# 05_LMS1_Misc.net
KiCad netlist of a schematic drawn in Altium Designer
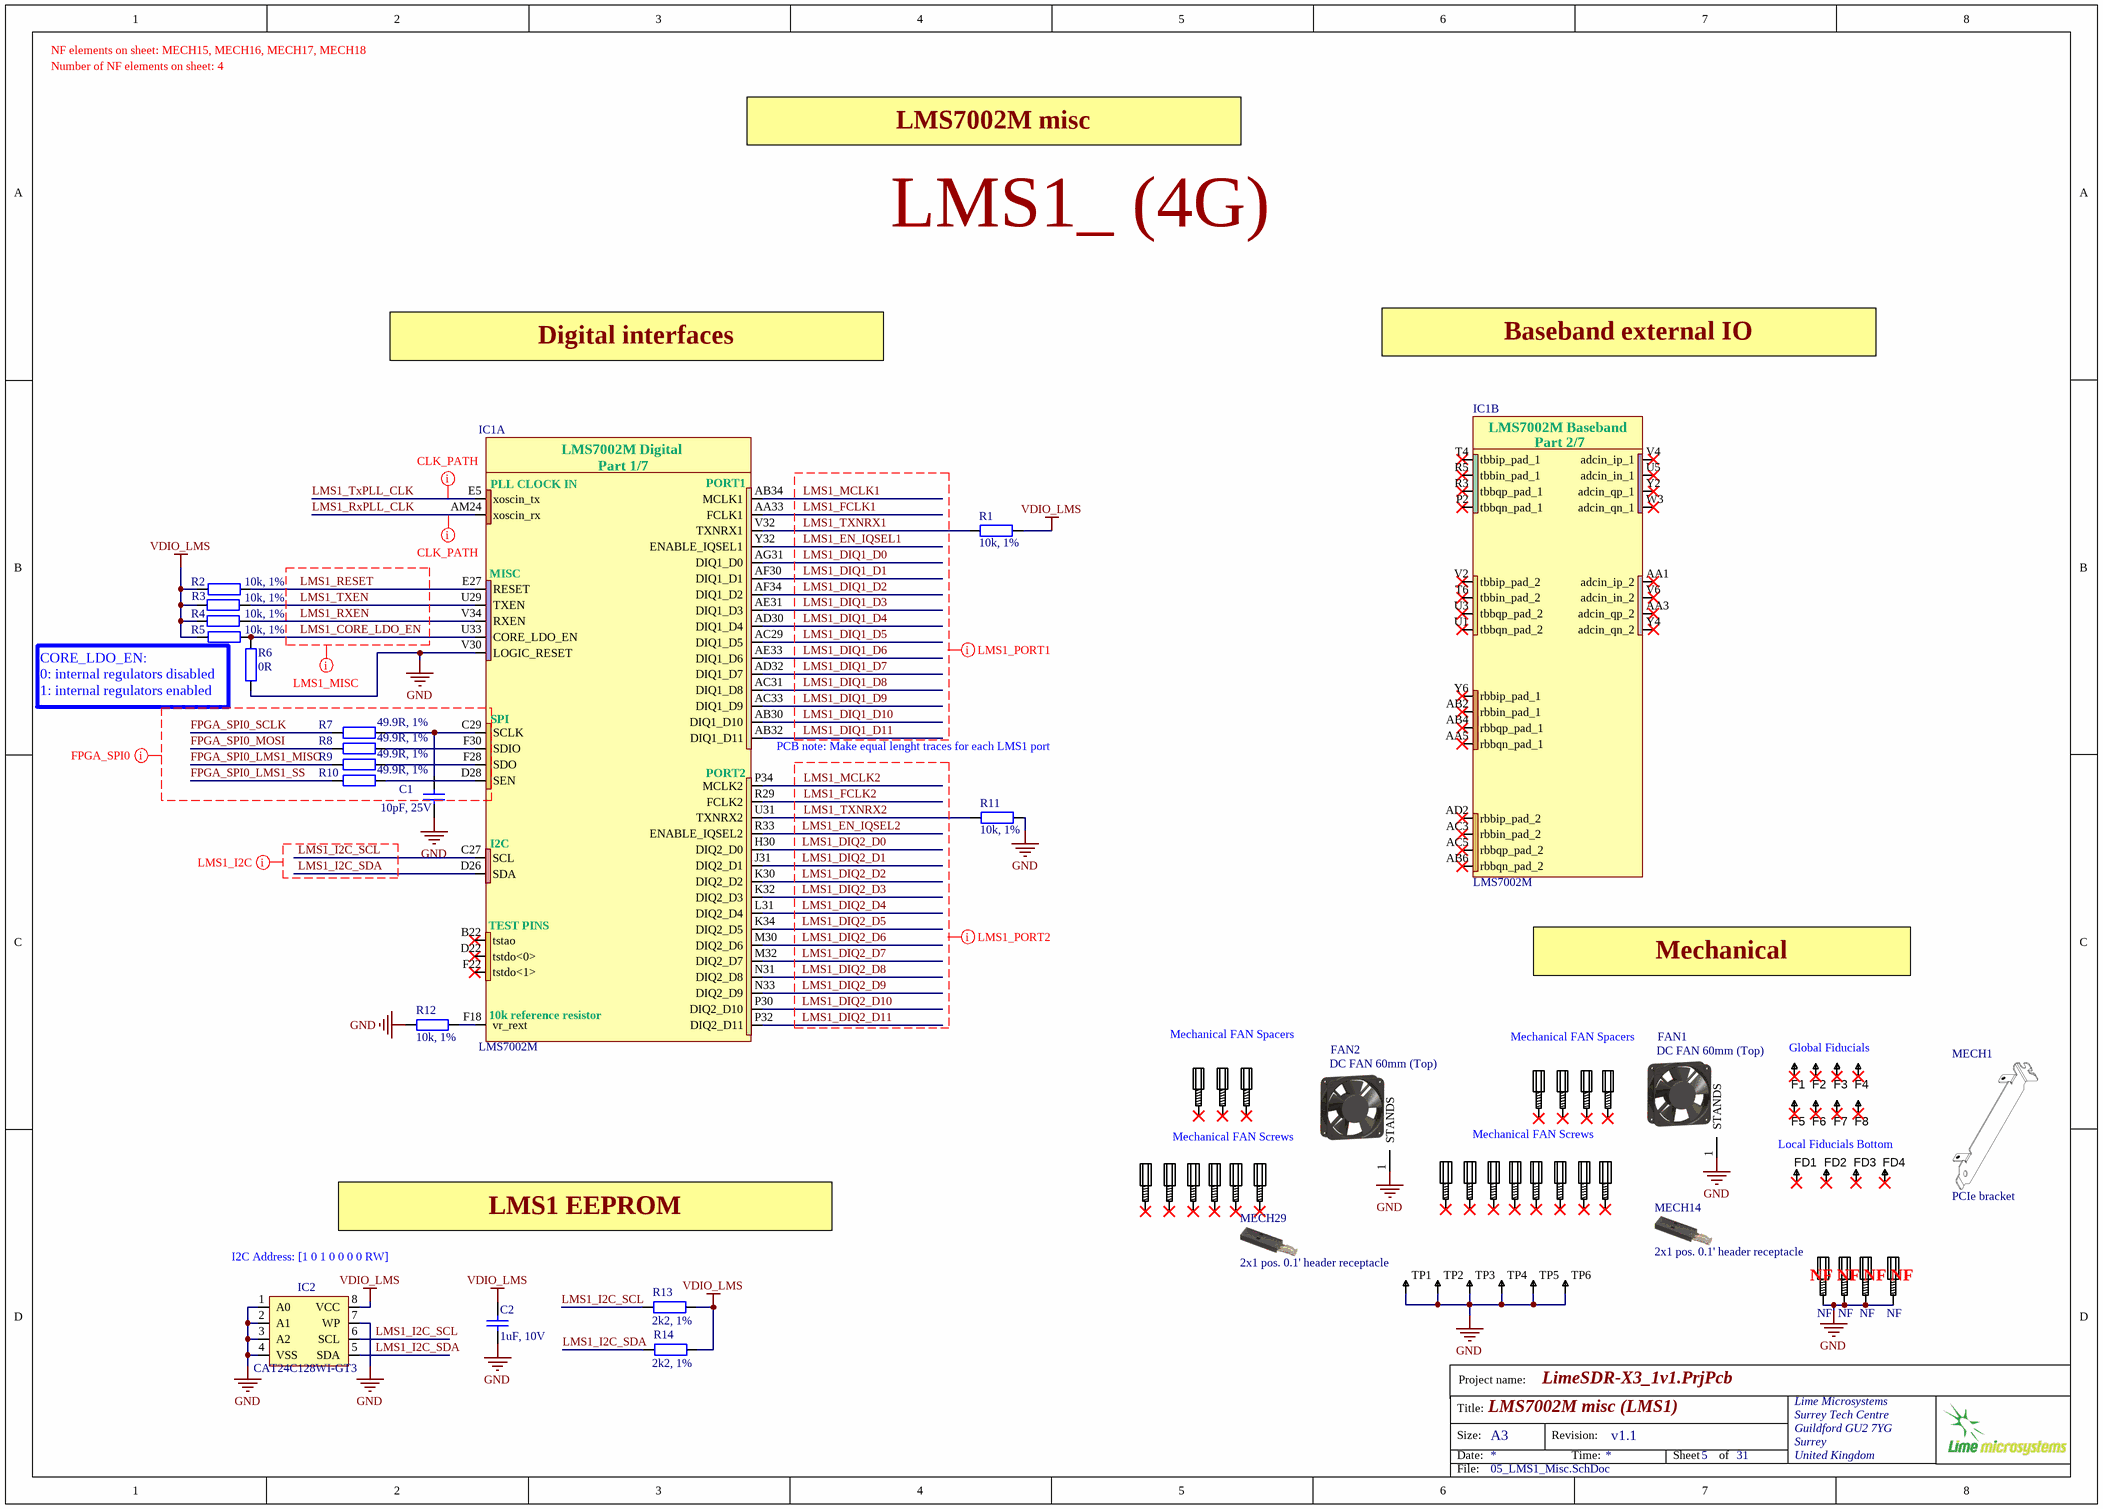
[diagram p0: 05_LMS1_Misc.SchDoc]

(export (version "E")
  (design (tool "Eeschema 10.0.6"))
  (components
    (comp (ref "C1")
      (value "10pF, 25V")
      (footprint "CAP0402")
      (fields (field (name "MANUFACTURER") "AVX"))
      (libsource (lib "") (part "Cap_0402_1"))
    )
    (comp (ref "C2")
      (value "1uF, 10V")
      (footprint "CAP0402")
      (fields (field (name "MANUFACTURER") "TDK"))
      (libsource (lib "LimeMicroAltiumLib_schLib") (part "Cap_0402"))
    )
    (comp (ref "F1")
      (value "Fiducial")
      (footprint "Fiducial")
      (libsource (lib "VGTU_Altium_lib") (part "Fiducial"))
    )
    (comp (ref "F2")
      (value "Fiducial")
      (footprint "Fiducial")
      (libsource (lib "VGTU_Altium_lib") (part "Fiducial"))
    )
    (comp (ref "F3")
      (value "Fiducial")
      (footprint "Fiducial")
      (libsource (lib "VGTU_Altium_lib") (part "Fiducial"))
    )
    (comp (ref "F4")
      (value "Fiducial")
      (footprint "Fiducial")
      (libsource (lib "VGTU_Altium_lib") (part "Fiducial"))
    )
    (comp (ref "F5")
      (value "Fiducial")
      (footprint "Fiducial")
      (libsource (lib "VGTU_Altium_lib") (part "Fiducial"))
    )
    (comp (ref "F6")
      (value "Fiducial")
      (footprint "Fiducial")
      (libsource (lib "VGTU_Altium_lib") (part "Fiducial"))
    )
    (comp (ref "F7")
      (value "Fiducial")
      (footprint "Fiducial")
      (libsource (lib "VGTU_Altium_lib") (part "Fiducial"))
    )
    (comp (ref "F8")
      (value "Fiducial")
      (footprint "Fiducial")
      (libsource (lib "VGTU_Altium_lib") (part "Fiducial"))
    )
    (comp (ref "FAN1")
      (value "DC FAN 60mm (Top)")
      (footprint "FAN_60mm")
      (fields (field (name "MANUFACTURER") "Sunon"))
      (libsource (lib "LimeMicroAltiumLib_schLib") (part "12V_DC_FAN"))
    )
    (comp (ref "FAN2")
      (value "DC FAN 60mm (Top)")
      (footprint "FAN_60mm")
      (fields (field (name "MANUFACTURER") "Sunon"))
      (libsource (lib "LimeMicroAltiumLib_schLib") (part "12V_DC_FAN"))
    )
    (comp (ref "FD1")
      (value "Fiducial")
      (footprint "Fiducial_local")
      (libsource (lib "") (part "Fiducial_1"))
    )
    (comp (ref "FD2")
      (value "Fiducial")
      (footprint "Fiducial_local")
      (libsource (lib "LimeMicroAltiumLib_schLib") (part "Fiducial"))
    )
    (comp (ref "FD3")
      (value "Fiducial")
      (footprint "Fiducial_local")
      (libsource (lib "") (part "Fiducial_2"))
    )
    (comp (ref "FD4")
      (value "Fiducial")
      (footprint "Fiducial_local")
      (libsource (lib "LimeMicroAltiumLib_schLib") (part "Fiducial"))
    )
    (comp (ref "IC1")
      (value "LMS7002M")
      (footprint "LMS7002M_v5")
      (description "Schematic symbol revision 4. Default footprint - 0.31mm pad")
      (fields (field (name "MANUFACTURER") "Lime Microsystems"))
      (libsource (lib "LimeMicroAltiumLib_schLib_r04") (part "LMS7002Mr4"))
    )
    (comp (ref "IC2")
      (value "CAT24C128WI-GT3")
      (footprint "SOIC127P600-8DL_v2")
      (fields (field (name "MANUFACTURER") "ON Semiconductor") (field (name "BASE PART NUMBER") "CAT24C128"))
      (libsource (lib "LimeMicroAltiumLib_schLib") (part "24FC64F"))
    )
    (comp (ref "MECH1")
      (value "PCIe bracket")
      (footprint "PCIe_bracket")
      (fields (field (name "MANUFACTURER") "Keystone Electronics"))
      (libsource (lib "LimeMicroAltiumLib_schLib_r01") (part "PCIe_bracket"))
    )
    (comp (ref "MECH2")
      (value "Spacer M3")
      (description "STANDOFF M/F MET 5MM HEX 10MM L")
      (fields (field (name "MANUFACTURER") "BOSSARD"))
      (libsource (lib "") (part "STANDOFF_M-F_THREADED_M3x8x10mm_HEX_5mm dia_1"))
    )
    (comp (ref "MECH3")
      (value "Spacer M3")
      (description "STANDOFF M/F MET 5MM HEX 10MM L")
      (fields (field (name "MANUFACTURER") "BOSSARD"))
      (libsource (lib "") (part "STANDOFF_M-F_THREADED_M3x8x10mm_HEX_5mm dia_1"))
    )
    (comp (ref "MECH4")
      (value "Spacer M3")
      (description "STANDOFF M/F MET 5MM HEX 10MM L")
      (fields (field (name "MANUFACTURER") "BOSSARD"))
      (libsource (lib "") (part "STANDOFF_M-F_THREADED_M3x8x10mm_HEX_5mm dia_1"))
    )
    (comp (ref "MECH5")
      (value "Spacer M3")
      (description "STANDOFF M/F MET 5MM HEX 10MM L")
      (fields (field (name "MANUFACTURER") "BOSSARD"))
      (libsource (lib "") (part "STANDOFF_M-F_THREADED_M3x8x10mm_HEX_5mm dia_1"))
    )
    (comp (ref "MECH6")
      (value "Screws M3")
      (description "STANDOFF M/F MET 5MM HEX 10MM L")
      (fields (field (name "MANUFACTURER") "BOSSARD"))
      (libsource (lib "LimeMicroAltiumLib_schLib") (part "STANDOFF_M-F_THREADED_M3x8x10mm_HEX_5mm dia"))
    )
    (comp (ref "MECH7")
      (value "Screws M3")
      (description "STANDOFF M/F MET 5MM HEX 10MM L")
      (fields (field (name "MANUFACTURER") "BOSSARD"))
      (libsource (lib "LimeMicroAltiumLib_schLib") (part "STANDOFF_M-F_THREADED_M3x8x10mm_HEX_5mm dia"))
    )
    (comp (ref "MECH8")
      (value "Screws M3")
      (description "STANDOFF M/F MET 5MM HEX 10MM L")
      (fields (field (name "MANUFACTURER") "BOSSARD"))
      (libsource (lib "LimeMicroAltiumLib_schLib") (part "STANDOFF_M-F_THREADED_M3x8x10mm_HEX_5mm dia"))
    )
    (comp (ref "MECH9")
      (value "Screws M3")
      (description "STANDOFF M/F MET 5MM HEX 10MM L")
      (fields (field (name "MANUFACTURER") "BOSSARD"))
      (libsource (lib "LimeMicroAltiumLib_schLib") (part "STANDOFF_M-F_THREADED_M3x8x10mm_HEX_5mm dia"))
    )
    (comp (ref "MECH10")
      (value "Screws M3")
      (description "STANDOFF M/F MET 5MM HEX 10MM L")
      (fields (field (name "MANUFACTURER") "BOSSARD"))
      (libsource (lib "LimeMicroAltiumLib_schLib") (part "STANDOFF_M-F_THREADED_M3x8x10mm_HEX_5mm dia"))
    )
    (comp (ref "MECH11")
      (value "Screws M3")
      (description "STANDOFF M/F MET 5MM HEX 10MM L")
      (fields (field (name "MANUFACTURER") "BOSSARD"))
      (libsource (lib "LimeMicroAltiumLib_schLib") (part "STANDOFF_M-F_THREADED_M3x8x10mm_HEX_5mm dia"))
    )
    (comp (ref "MECH12")
      (value "Screws M3")
      (description "STANDOFF M/F MET 5MM HEX 10MM L")
      (fields (field (name "MANUFACTURER") "BOSSARD"))
      (libsource (lib "LimeMicroAltiumLib_schLib") (part "STANDOFF_M-F_THREADED_M3x8x10mm_HEX_5mm dia"))
    )
    (comp (ref "MECH13")
      (value "Screws M3")
      (description "STANDOFF M/F MET 5MM HEX 10MM L")
      (fields (field (name "MANUFACTURER") "BOSSARD"))
      (libsource (lib "LimeMicroAltiumLib_schLib") (part "STANDOFF_M-F_THREADED_M3x8x10mm_HEX_5mm dia"))
    )
    (comp (ref "MECH14")
      (value "2x1 pos. 0.1' header receptacle")
      (fields (field (name "MANUFACTURER") "Molex"))
      (libsource (lib "LimeMicroAltiumLib_schLib_r01") (part "Header_1x2_receptacle"))
    )
    (comp (ref "MECH15")
      (value "Standoff")
      (footprint "PCB_standoff")
      (description "STANDOFF M/F MET 5MM HEX 10MM L")
      (fields (field (name "MANUFACTURER") "FIX&FASTEN") (field (name "ASSEMBLY INFO") "NF"))
      (libsource (lib "LimeMicroAltiumLib_schLib") (part "STANDOFF_M-F_THREADED_M3x8x10mm_HEX_5mm dia"))
    )
    (comp (ref "MECH16")
      (value "Standoff")
      (footprint "PCB_standoff")
      (description "STANDOFF M/F MET 5MM HEX 10MM L")
      (fields (field (name "MANUFACTURER") "FIX&FASTEN") (field (name "ASSEMBLY INFO") "NF"))
      (libsource (lib "LimeMicroAltiumLib_schLib") (part "STANDOFF_M-F_THREADED_M3x8x10mm_HEX_5mm dia"))
    )
    (comp (ref "MECH17")
      (value "Standoff")
      (footprint "PCB_standoff")
      (description "STANDOFF M/F MET 5MM HEX 10MM L")
      (fields (field (name "MANUFACTURER") "FIX&FASTEN") (field (name "ASSEMBLY INFO") "NF"))
      (libsource (lib "LimeMicroAltiumLib_schLib") (part "STANDOFF_M-F_THREADED_M3x8x10mm_HEX_5mm dia"))
    )
    (comp (ref "MECH18")
      (value "Standoff")
      (footprint "PCB_standoff")
      (description "STANDOFF M/F MET 5MM HEX 10MM L")
      (fields (field (name "MANUFACTURER") "FIX&FASTEN") (field (name "ASSEMBLY INFO") "NF"))
      (libsource (lib "") (part "STANDOFF_M-F_THREADED_M3x8x10mm_HEX_5mm dia_2"))
    )
    (comp (ref "MECH20")
      (value "Spacer M3")
      (description "STANDOFF M/F MET 5MM HEX 10MM L")
      (fields (field (name "MANUFACTURER") "BOSSARD"))
      (libsource (lib "") (part "STANDOFF_M-F_THREADED_M3x8x10mm_HEX_5mm dia_1"))
    )
    (comp (ref "MECH21")
      (value "Spacer M3")
      (description "STANDOFF M/F MET 5MM HEX 10MM L")
      (fields (field (name "MANUFACTURER") "BOSSARD"))
      (libsource (lib "") (part "STANDOFF_M-F_THREADED_M3x8x10mm_HEX_5mm dia_1"))
    )
    (comp (ref "MECH22")
      (value "Spacer M3")
      (description "STANDOFF M/F MET 5MM HEX 10MM L")
      (fields (field (name "MANUFACTURER") "BOSSARD"))
      (libsource (lib "") (part "STANDOFF_M-F_THREADED_M3x8x10mm_HEX_5mm dia_1"))
    )
    (comp (ref "MECH23")
      (value "Screws M3")
      (description "STANDOFF M/F MET 5MM HEX 10MM L")
      (fields (field (name "MANUFACTURER") "BOSSARD"))
      (libsource (lib "LimeMicroAltiumLib_schLib") (part "STANDOFF_M-F_THREADED_M3x8x10mm_HEX_5mm dia"))
    )
    (comp (ref "MECH24")
      (value "Screws M3")
      (description "STANDOFF M/F MET 5MM HEX 10MM L")
      (fields (field (name "MANUFACTURER") "BOSSARD"))
      (libsource (lib "LimeMicroAltiumLib_schLib") (part "STANDOFF_M-F_THREADED_M3x8x10mm_HEX_5mm dia"))
    )
    (comp (ref "MECH25")
      (value "Screws M3")
      (description "STANDOFF M/F MET 5MM HEX 10MM L")
      (fields (field (name "MANUFACTURER") "BOSSARD"))
      (libsource (lib "LimeMicroAltiumLib_schLib") (part "STANDOFF_M-F_THREADED_M3x8x10mm_HEX_5mm dia"))
    )
    (comp (ref "MECH26")
      (value "Screws M3")
      (description "STANDOFF M/F MET 5MM HEX 10MM L")
      (fields (field (name "MANUFACTURER") "BOSSARD"))
      (libsource (lib "LimeMicroAltiumLib_schLib") (part "STANDOFF_M-F_THREADED_M3x8x10mm_HEX_5mm dia"))
    )
    (comp (ref "MECH27")
      (value "Screws M3")
      (description "STANDOFF M/F MET 5MM HEX 10MM L")
      (fields (field (name "MANUFACTURER") "BOSSARD"))
      (libsource (lib "LimeMicroAltiumLib_schLib") (part "STANDOFF_M-F_THREADED_M3x8x10mm_HEX_5mm dia"))
    )
    (comp (ref "MECH28")
      (value "Screws M3")
      (description "STANDOFF M/F MET 5MM HEX 10MM L")
      (fields (field (name "MANUFACTURER") "BOSSARD"))
      (libsource (lib "LimeMicroAltiumLib_schLib") (part "STANDOFF_M-F_THREADED_M3x8x10mm_HEX_5mm dia"))
    )
    (comp (ref "MECH29")
      (value "2x1 pos. 0.1' header receptacle")
      (fields (field (name "MANUFACTURER") "Molex"))
      (libsource (lib "LimeMicroAltiumLib_schLib_r01") (part "Header_1x2_receptacle"))
    )
    (comp (ref "R1")
      (value "10k, 1%")
      (footprint "RES0402")
      (fields (field (name "MANUFACTURER") "Yageo") (field (name "TOLERANCE") "±1%"))
      (libsource (lib "LimeMicroAltiumLib_schLib") (part "Res_0402"))
    )
    (comp (ref "R2")
      (value "10k, 1%")
      (footprint "RES0402")
      (fields (field (name "MANUFACTURER") "Yageo") (field (name "TOLERANCE") "±1%"))
      (libsource (lib "LimeMicroAltiumLib_schLib") (part "Res_0402"))
    )
    (comp (ref "R3")
      (value "10k, 1%")
      (footprint "RES0402")
      (fields (field (name "MANUFACTURER") "Yageo") (field (name "TOLERANCE") "±1%"))
      (libsource (lib "LimeMicroAltiumLib_schLib") (part "Res_0402"))
    )
    (comp (ref "R4")
      (value "10k, 1%")
      (footprint "RES0402")
      (fields (field (name "MANUFACTURER") "Yageo") (field (name "TOLERANCE") "±1%"))
      (libsource (lib "LimeMicroAltiumLib_schLib") (part "Res_0402"))
    )
    (comp (ref "R5")
      (value "10k, 1%")
      (footprint "RES0402")
      (fields (field (name "MANUFACTURER") "Yageo") (field (name "TOLERANCE") "±1%"))
      (libsource (lib "LimeMicroAltiumLib_schLib") (part "Res_0402"))
    )
    (comp (ref "R6")
      (value "0R")
      (footprint "RES0402")
      (fields (field (name "MANUFACTURER") "Yageo") (field (name "TOLERANCE") "Jumper"))
      (libsource (lib "LimeMicroAltiumLib_schLib") (part "Res_0402"))
    )
    (comp (ref "R7")
      (value "49.9R, 1%")
      (footprint "RES0402")
      (fields
        (field (name "TOLERANCE") "±1%")
        (field (name "MANUFACTURER") "Samsung Electro-Mechanics America, Inc.")
        (field (name "MANUFACTURER PART NUMBER") "RC1005F49R9CS")
      )
      (libsource (lib "LimeMicroAltiumLib_schLib") (part "Res_0402"))
    )
    (comp (ref "R8")
      (value "49.9R, 1%")
      (footprint "RES0402")
      (fields
        (field (name "TOLERANCE") "±1%")
        (field (name "MANUFACTURER") "Samsung Electro-Mechanics America, Inc.")
        (field (name "MANUFACTURER PART NUMBER") "RC1005F49R9CS")
      )
      (libsource (lib "LimeMicroAltiumLib_schLib") (part "Res_0402"))
    )
    (comp (ref "R9")
      (value "49.9R, 1%")
      (footprint "RES0402")
      (fields
        (field (name "TOLERANCE") "±1%")
        (field (name "MANUFACTURER") "Samsung Electro-Mechanics America, Inc.")
        (field (name "MANUFACTURER PART NUMBER") "RC1005F49R9CS")
      )
      (libsource (lib "LimeMicroAltiumLib_schLib") (part "Res_0402"))
    )
    (comp (ref "R10")
      (value "49.9R, 1%")
      (footprint "RES0402")
      (fields
        (field (name "TOLERANCE") "±1%")
        (field (name "MANUFACTURER") "Samsung Electro-Mechanics America, Inc.")
        (field (name "MANUFACTURER PART NUMBER") "RC1005F49R9CS")
      )
      (libsource (lib "LimeMicroAltiumLib_schLib") (part "Res_0402"))
    )
    (comp (ref "R11")
      (value "10k, 1%")
      (footprint "RES0402")
      (fields (field (name "MANUFACTURER") "Yageo") (field (name "TOLERANCE") "±1%"))
      (libsource (lib "LimeMicroAltiumLib_schLib") (part "Res_0402"))
    )
    (comp (ref "R12")
      (value "10k, 1%")
      (footprint "RES0402")
      (fields (field (name "MANUFACTURER") "Yageo") (field (name "TOLERANCE") "±1%"))
      (libsource (lib "") (part "Res_0402_1"))
    )
    (comp (ref "R13")
      (value "2k2, 1%")
      (footprint "RES0402")
      (fields (field (name "MANUFACTURER") "Stackpole Electronics Inc") (field (name "TOLERANCE") "±1%"))
      (libsource (lib "LimeMicroAltiumLib_schLib") (part "Res_0402"))
    )
    (comp (ref "R14")
      (value "2k2, 1%")
      (footprint "RES0402")
      (fields (field (name "MANUFACTURER") "Stackpole Electronics Inc") (field (name "TOLERANCE") "±1%"))
      (libsource (lib "LimeMicroAltiumLib_schLib") (part "Res_0402"))
    )
    (comp (ref "TP1")
      (value "TESTPOINT_THT_MINI")
      (footprint "TP-SMD-LOW_PROFILE")
      (description "Test Point PCB mount Miniature White")
      (fields (field (name "MANUFACTURER") "Harwin Inc"))
      (libsource (lib "LimeMicroAltiumLib_schLib") (part "TESTPOINT_THT_MINI"))
    )
    (comp (ref "TP2")
      (value "TESTPOINT_THT_MINI")
      (footprint "TP-SMD-LOW_PROFILE")
      (description "Test Point PCB mount Miniature White")
      (fields (field (name "MANUFACTURER") "Harwin Inc"))
      (libsource (lib "LimeMicroAltiumLib_schLib") (part "TESTPOINT_THT_MINI"))
    )
    (comp (ref "TP3")
      (value "TESTPOINT_THT_MINI")
      (footprint "TP-SMD-LOW_PROFILE")
      (description "Test Point PCB mount Miniature White")
      (fields (field (name "MANUFACTURER") "Harwin Inc"))
      (libsource (lib "LimeMicroAltiumLib_schLib") (part "TESTPOINT_THT_MINI"))
    )
    (comp (ref "TP4")
      (value "TESTPOINT_THT_MINI")
      (footprint "TP-SMD-LOW_PROFILE")
      (description "Test Point PCB mount Miniature White")
      (fields (field (name "MANUFACTURER") "Harwin Inc"))
      (libsource (lib "LimeMicroAltiumLib_schLib") (part "TESTPOINT_THT_MINI"))
    )
    (comp (ref "TP5")
      (value "TESTPOINT_THT_MINI")
      (footprint "TP-SMD-LOW_PROFILE")
      (description "Test Point PCB mount Miniature White")
      (fields (field (name "MANUFACTURER") "Harwin Inc"))
      (libsource (lib "LimeMicroAltiumLib_schLib") (part "TESTPOINT_THT_MINI"))
    )
    (comp (ref "TP6")
      (value "TESTPOINT_THT_MINI")
      (footprint "TP-SMD-LOW_PROFILE")
      (description "Test Point PCB mount Miniature White")
      (fields (field (name "MANUFACTURER") "Harwin Inc"))
      (libsource (lib "LimeMicroAltiumLib_schLib") (part "TESTPOINT_THT_MINI"))
    )
  )
  (nets
    (net (code "1") (name "/FPGA_SPI0_LMS1_MISO") (class "Default")
      (node (ref "R9") (pin "2") (pinfunction "2_2") (pintype "passive"))
    )
    (net (code "2") (name "/FPGA_SPI0_LMS1_SS") (class "Default")
      (node (ref "R10") (pin "2") (pinfunction "2_2") (pintype "passive"))
    )
    (net (code "3") (name "/FPGA_SPI0_MOSI") (class "Default")
      (node (ref "R8") (pin "2") (pinfunction "2_2") (pintype "passive"))
    )
    (net (code "4") (name "/FPGA_SPI0_SCLK") (class "Default")
      (node (ref "R7") (pin "2") (pinfunction "2_2") (pintype "passive"))
    )
    (net (code "5") (name "/LMS1_CORE_LDO_EN") (class "Default")
      (node (ref "IC1") (pin "U33") (pinfunction "CORE_LDO_EN_U33") (pintype "passive"))
      (node (ref "R5") (pin "1") (pinfunction "1_1") (pintype "passive"))
      (node (ref "R6") (pin "2") (pinfunction "2_2") (pintype "passive"))
    )
    (net (code "6") (name "/LMS1_DIQ1_D0") (class "Default")
      (node (ref "IC1") (pin "AG31") (pinfunction "DIQ1_D0_AG31") (pintype "passive"))
    )
    (net (code "7") (name "/LMS1_DIQ1_D1") (class "Default")
      (node (ref "IC1") (pin "AF30") (pinfunction "DIQ1_D1_AF30") (pintype "passive"))
    )
    (net (code "8") (name "/LMS1_DIQ1_D2") (class "Default")
      (node (ref "IC1") (pin "AF34") (pinfunction "DIQ1_D2_AF34") (pintype "passive"))
    )
    (net (code "9") (name "/LMS1_DIQ1_D3") (class "Default")
      (node (ref "IC1") (pin "AE31") (pinfunction "DIQ1_D3_AE31") (pintype "passive"))
    )
    (net (code "10") (name "/LMS1_DIQ1_D4") (class "Default")
      (node (ref "IC1") (pin "AD30") (pinfunction "DIQ1_D4_AD30") (pintype "passive"))
    )
    (net (code "11") (name "/LMS1_DIQ1_D5") (class "Default")
      (node (ref "IC1") (pin "AC29") (pinfunction "DIQ1_D5_AC29") (pintype "passive"))
    )
    (net (code "12") (name "/LMS1_DIQ1_D6") (class "Default")
      (node (ref "IC1") (pin "AE33") (pinfunction "DIQ1_D6_AE33") (pintype "passive"))
    )
    (net (code "13") (name "/LMS1_DIQ1_D7") (class "Default")
      (node (ref "IC1") (pin "AD32") (pinfunction "DIQ1_D7_AD32") (pintype "passive"))
    )
    (net (code "14") (name "/LMS1_DIQ1_D8") (class "Default")
      (node (ref "IC1") (pin "AC31") (pinfunction "DIQ1_D8_AC31") (pintype "passive"))
    )
    (net (code "15") (name "/LMS1_DIQ1_D9") (class "Default")
      (node (ref "IC1") (pin "AC33") (pinfunction "DIQ1_D9_AC33") (pintype "passive"))
    )
    (net (code "16") (name "/LMS1_DIQ1_D10") (class "Default")
      (node (ref "IC1") (pin "AB30") (pinfunction "DIQ1_D10_AB30") (pintype "passive"))
    )
    (net (code "17") (name "/LMS1_DIQ1_D11") (class "Default")
      (node (ref "IC1") (pin "AB32") (pinfunction "DIQ1_D11_AB32") (pintype "passive"))
    )
    (net (code "18") (name "/LMS1_DIQ2_D0") (class "Default")
      (node (ref "IC1") (pin "H30") (pinfunction "DIQ2_D0_H30") (pintype "passive"))
    )
    (net (code "19") (name "/LMS1_DIQ2_D1") (class "Default")
      (node (ref "IC1") (pin "J31") (pinfunction "DIQ2_D1_J31") (pintype "passive"))
    )
    (net (code "20") (name "/LMS1_DIQ2_D2") (class "Default")
      (node (ref "IC1") (pin "K30") (pinfunction "DIQ2_D2_K30") (pintype "passive"))
    )
    (net (code "21") (name "/LMS1_DIQ2_D3") (class "Default")
      (node (ref "IC1") (pin "K32") (pinfunction "DIQ2_D3_K32") (pintype "passive"))
    )
    (net (code "22") (name "/LMS1_DIQ2_D4") (class "Default")
      (node (ref "IC1") (pin "L31") (pinfunction "DIQ2_D4_L31") (pintype "passive"))
    )
    (net (code "23") (name "/LMS1_DIQ2_D5") (class "Default")
      (node (ref "IC1") (pin "K34") (pinfunction "DIQ2_D5_K34") (pintype "passive"))
    )
    (net (code "24") (name "/LMS1_DIQ2_D6") (class "Default")
      (node (ref "IC1") (pin "M30") (pinfunction "DIQ2_D6_M30") (pintype "passive"))
    )
    (net (code "25") (name "/LMS1_DIQ2_D7") (class "Default")
      (node (ref "IC1") (pin "M32") (pinfunction "DIQ2_D7_M32") (pintype "passive"))
    )
    (net (code "26") (name "/LMS1_DIQ2_D8") (class "Default")
      (node (ref "IC1") (pin "N31") (pinfunction "DIQ2_D8_N31") (pintype "passive"))
    )
    (net (code "27") (name "/LMS1_DIQ2_D9") (class "Default")
      (node (ref "IC1") (pin "N33") (pinfunction "DIQ2_D9_N33") (pintype "passive"))
    )
    (net (code "28") (name "/LMS1_DIQ2_D10") (class "Default")
      (node (ref "IC1") (pin "P30") (pinfunction "DIQ2_D10_P30") (pintype "passive"))
    )
    (net (code "29") (name "/LMS1_DIQ2_D11") (class "Default")
      (node (ref "IC1") (pin "P32") (pinfunction "DIQ2_D11_P32") (pintype "passive"))
    )
    (net (code "30") (name "/LMS1_EN_IQSEL1") (class "Default")
      (node (ref "IC1") (pin "Y32") (pinfunction "ENABLE_IQSEL1_Y32") (pintype "passive"))
    )
    (net (code "31") (name "/LMS1_EN_IQSEL2") (class "Default")
      (node (ref "IC1") (pin "R33") (pinfunction "ENABLE_IQSEL2_R33") (pintype "passive"))
    )
    (net (code "32") (name "/LMS1_FCLK1") (class "Default")
      (node (ref "IC1") (pin "AA33") (pinfunction "FCLK1_AA33") (pintype "passive"))
    )
    (net (code "33") (name "/LMS1_FCLK2") (class "Default")
      (node (ref "IC1") (pin "R29") (pinfunction "FCLK2_R29") (pintype "passive"))
    )
    (net (code "34") (name "/LMS1_I2C_SCL") (class "Default")
      (node (ref "IC1") (pin "C27") (pinfunction "SCL_C27") (pintype "passive"))
      (node (ref "IC2") (pin "6") (pinfunction "SCL_6") (pintype "passive"))
      (node (ref "R13") (pin "2") (pinfunction "2_2") (pintype "passive"))
    )
    (net (code "35") (name "/LMS1_I2C_SDA") (class "Default")
      (node (ref "IC1") (pin "D26") (pinfunction "SDA_D26") (pintype "passive"))
      (node (ref "IC2") (pin "5") (pinfunction "SDA_5") (pintype "passive"))
      (node (ref "R14") (pin "2") (pinfunction "2_2") (pintype "passive"))
    )
    (net (code "36") (name "/LMS1_MCLK1") (class "Default")
      (node (ref "IC1") (pin "AB34") (pinfunction "MCLK1_AB34") (pintype "passive"))
    )
    (net (code "37") (name "/LMS1_MCLK2") (class "Default")
      (node (ref "IC1") (pin "P34") (pinfunction "MCLK2_P34") (pintype "passive"))
    )
    (net (code "38") (name "/LMS1_RESET") (class "Default")
      (node (ref "IC1") (pin "E27") (pinfunction "RESET_E27") (pintype "passive"))
      (node (ref "R2") (pin "1") (pinfunction "1_1") (pintype "passive"))
    )
    (net (code "39") (name "/LMS1_RXEN") (class "Default")
      (node (ref "IC1") (pin "V34") (pinfunction "RXEN_V34") (pintype "passive"))
      (node (ref "R4") (pin "2") (pinfunction "2_2") (pintype "passive"))
    )
    (net (code "40") (name "/LMS1_RxPLL_CLK") (class "Default")
      (node (ref "IC1") (pin "AM24") (pinfunction "xoscin_rx_AM24") (pintype "passive"))
    )
    (net (code "41") (name "/LMS1_TXEN") (class "Default")
      (node (ref "IC1") (pin "U29") (pinfunction "TXEN_U29") (pintype "passive"))
      (node (ref "R3") (pin "2") (pinfunction "2_2") (pintype "passive"))
    )
    (net (code "42") (name "/LMS1_TXNRX1") (class "Default")
      (node (ref "IC1") (pin "V32") (pinfunction "TXNRX1_V32") (pintype "passive"))
      (node (ref "R1") (pin "1") (pinfunction "1_1") (pintype "passive"))
    )
    (net (code "43") (name "/LMS1_TXNRX2") (class "Default")
      (node (ref "IC1") (pin "U31") (pinfunction "TXNRX2_U31") (pintype "passive"))
      (node (ref "R11") (pin "2") (pinfunction "2_2") (pintype "passive"))
    )
    (net (code "44") (name "/LMS1_TxPLL_CLK") (class "Default")
      (node (ref "IC1") (pin "E5") (pinfunction "xoscin_tx_E5") (pintype "passive"))
    )
    (net (code "45") (name "GND") (class "Default")
      (node (ref "C1") (pin "2") (pinfunction "2_2") (pintype "passive"))
      (node (ref "C2") (pin "2") (pinfunction "2_2") (pintype "passive"))
      (node (ref "FAN1") (pin "1") (pinfunction "STANDS_1") (pintype "passive"))
      (node (ref "FAN2") (pin "1") (pinfunction "STANDS_1") (pintype "passive"))
      (node (ref "IC1") (pin "V30") (pinfunction "LOGIC_RESET_V30") (pintype "passive"))
      (node (ref "IC2") (pin "1") (pinfunction "A0_1") (pintype "passive"))
      (node (ref "IC2") (pin "2") (pinfunction "A1_2") (pintype "passive"))
      (node (ref "IC2") (pin "3") (pinfunction "A2_3") (pintype "passive"))
      (node (ref "IC2") (pin "4") (pinfunction "VSS_4") (pintype "passive"))
      (node (ref "IC2") (pin "7") (pinfunction "WP_7") (pintype "passive"))
      (node (ref "MECH15") (pin "MH1") (pinfunction "MH1_MH1") (pintype "passive"))
      (node (ref "MECH16") (pin "MH1") (pinfunction "MH1_MH1") (pintype "passive"))
      (node (ref "MECH17") (pin "MH1") (pinfunction "MH1_MH1") (pintype "passive"))
      (node (ref "MECH18") (pin "MH1") (pinfunction "MH1_MH1") (pintype "passive"))
      (node (ref "R11") (pin "1") (pinfunction "1_1") (pintype "passive"))
      (node (ref "R12") (pin "2") (pinfunction "2_2") (pintype "passive"))
      (node (ref "R6") (pin "1") (pinfunction "1_1") (pintype "passive"))
      (node (ref "TP1") (pin "1") (pintype "passive"))
      (node (ref "TP2") (pin "1") (pintype "passive"))
      (node (ref "TP3") (pin "1") (pintype "passive"))
      (node (ref "TP4") (pin "1") (pintype "passive"))
      (node (ref "TP5") (pin "1") (pintype "passive"))
      (node (ref "TP6") (pin "1") (pintype "passive"))
    )
    (net (code "46") (name "Net-(IC1A-SCLK)") (class "Default")
      (node (ref "C1") (pin "1") (pinfunction "1_1") (pintype "passive"))
      (node (ref "IC1") (pin "C29") (pinfunction "SCLK_C29") (pintype "passive"))
      (node (ref "R7") (pin "1") (pinfunction "1_1") (pintype "passive"))
    )
    (net (code "47") (name "Net-(IC1A-SDIO)") (class "Default")
      (node (ref "IC1") (pin "F30") (pinfunction "SDIO_F30") (pintype "passive"))
      (node (ref "R8") (pin "1") (pinfunction "1_1") (pintype "passive"))
    )
    (net (code "48") (name "Net-(IC1A-SDO)") (class "Default")
      (node (ref "IC1") (pin "F28") (pinfunction "SDO_F28") (pintype "passive"))
      (node (ref "R9") (pin "1") (pinfunction "1_1") (pintype "passive"))
    )
    (net (code "49") (name "Net-(IC1A-SEN)") (class "Default")
      (node (ref "IC1") (pin "D28") (pinfunction "SEN_D28") (pintype "passive"))
      (node (ref "R10") (pin "1") (pinfunction "1_1") (pintype "passive"))
    )
    (net (code "50") (name "Net-(IC1A-vr_rext)") (class "Default")
      (node (ref "IC1") (pin "F18") (pinfunction "vr_rext_F18") (pintype "passive"))
      (node (ref "R12") (pin "1") (pinfunction "1_1") (pintype "passive"))
    )
    (net (code "51") (name "VDIO_LMS") (class "Default")
      (node (ref "C2") (pin "1") (pinfunction "1_1") (pintype "passive"))
      (node (ref "IC2") (pin "8") (pinfunction "VCC_8") (pintype "passive"))
      (node (ref "R1") (pin "2") (pinfunction "2_2") (pintype "passive"))
      (node (ref "R13") (pin "1") (pinfunction "1_1") (pintype "passive"))
      (node (ref "R14") (pin "1") (pinfunction "1_1") (pintype "passive"))
      (node (ref "R2") (pin "2") (pinfunction "2_2") (pintype "passive"))
      (node (ref "R3") (pin "1") (pinfunction "1_1") (pintype "passive"))
      (node (ref "R4") (pin "1") (pinfunction "1_1") (pintype "passive"))
      (node (ref "R5") (pin "2") (pinfunction "2_2") (pintype "passive"))
    )
    (net (code "52") (name "unconnected-(F1-Pad1)") (class "Default")
      (node (ref "F1") (pin "1") (pintype "passive+no_connect"))
    )
    (net (code "53") (name "unconnected-(F2-Pad1)") (class "Default")
      (node (ref "F2") (pin "1") (pintype "passive+no_connect"))
    )
    (net (code "54") (name "unconnected-(F3-Pad1)") (class "Default")
      (node (ref "F3") (pin "1") (pintype "passive+no_connect"))
    )
    (net (code "55") (name "unconnected-(F4-Pad1)") (class "Default")
      (node (ref "F4") (pin "1") (pintype "passive+no_connect"))
    )
    (net (code "56") (name "unconnected-(F5-Pad1)") (class "Default")
      (node (ref "F5") (pin "1") (pintype "passive+no_connect"))
    )
    (net (code "57") (name "unconnected-(F6-Pad1)") (class "Default")
      (node (ref "F6") (pin "1") (pintype "passive+no_connect"))
    )
    (net (code "58") (name "unconnected-(F7-Pad1)") (class "Default")
      (node (ref "F7") (pin "1") (pintype "passive+no_connect"))
    )
    (net (code "59") (name "unconnected-(F8-Pad1)") (class "Default")
      (node (ref "F8") (pin "1") (pintype "passive+no_connect"))
    )
    (net (code "60") (name "unconnected-(FD1-Pad1)") (class "Default")
      (node (ref "FD1") (pin "1") (pintype "passive+no_connect"))
    )
    (net (code "61") (name "unconnected-(FD2-Pad1)") (class "Default")
      (node (ref "FD2") (pin "1") (pintype "passive+no_connect"))
    )
    (net (code "62") (name "unconnected-(FD3-Pad1)") (class "Default")
      (node (ref "FD3") (pin "1") (pintype "passive+no_connect"))
    )
    (net (code "63") (name "unconnected-(FD4-Pad1)") (class "Default")
      (node (ref "FD4") (pin "1") (pintype "passive+no_connect"))
    )
    (net (code "64") (name "unconnected-(IC1A-tstao-PadB22)") (class "Default")
      (node (ref "IC1") (pin "B22") (pinfunction "tstao_B22") (pintype "passive"))
    )
    (net (code "65") (name "unconnected-(IC1A-tstdo<0>-PadD22)") (class "Default")
      (node (ref "IC1") (pin "D22") (pinfunction "tstdo<0>_D22") (pintype "passive"))
    )
    (net (code "66") (name "unconnected-(IC1A-tstdo<1>-PadF22)") (class "Default")
      (node (ref "IC1") (pin "F22") (pinfunction "tstdo<1>_F22") (pintype "passive"))
    )
    (net (code "67") (name "unconnected-(IC1B-adcin_in_1-PadU5)") (class "Default")
      (node (ref "IC1") (pin "U5") (pinfunction "adcin_in_1_U5") (pintype "passive+no_connect"))
    )
    (net (code "68") (name "unconnected-(IC1B-adcin_in_2-PadV6)") (class "Default")
      (node (ref "IC1") (pin "V6") (pinfunction "adcin_in_2_V6") (pintype "passive+no_connect"))
    )
    (net (code "69") (name "unconnected-(IC1B-adcin_ip_1-PadV4)") (class "Default")
      (node (ref "IC1") (pin "V4") (pinfunction "adcin_ip_1_V4") (pintype "passive+no_connect"))
    )
    (net (code "70") (name "unconnected-(IC1B-adcin_ip_2-PadAA1)") (class "Default")
      (node (ref "IC1") (pin "AA1") (pinfunction "adcin_ip_2_AA1") (pintype "passive+no_connect"))
    )
    (net (code "71") (name "unconnected-(IC1B-adcin_qn_1-PadW3)") (class "Default")
      (node (ref "IC1") (pin "W3") (pinfunction "adcin_qn_1_W3") (pintype "passive+no_connect"))
    )
    (net (code "72") (name "unconnected-(IC1B-adcin_qn_2-PadY4)") (class "Default")
      (node (ref "IC1") (pin "Y4") (pinfunction "adcin_qn_2_Y4") (pintype "passive+no_connect"))
    )
    (net (code "73") (name "unconnected-(IC1B-adcin_qp_1-PadY2)") (class "Default")
      (node (ref "IC1") (pin "Y2") (pinfunction "adcin_qp_1_Y2") (pintype "passive+no_connect"))
    )
    (net (code "74") (name "unconnected-(IC1B-adcin_qp_2-PadAA3)") (class "Default")
      (node (ref "IC1") (pin "AA3") (pinfunction "adcin_qp_2_AA3") (pintype "passive+no_connect"))
    )
    (net (code "75") (name "unconnected-(IC1B-rbbin_pad_1-PadAB2)") (class "Default")
      (node (ref "IC1") (pin "AB2") (pinfunction "rbbin_pad_1_AB2") (pintype "passive+no_connect"))
    )
    (net (code "76") (name "unconnected-(IC1B-rbbin_pad_2-PadAC3)") (class "Default")
      (node (ref "IC1") (pin "AC3") (pinfunction "rbbin_pad_2_AC3") (pintype "passive+no_connect"))
    )
    (net (code "77") (name "unconnected-(IC1B-rbbip_pad_1-PadY6)") (class "Default")
      (node (ref "IC1") (pin "Y6") (pinfunction "rbbip_pad_1_Y6") (pintype "passive+no_connect"))
    )
    (net (code "78") (name "unconnected-(IC1B-rbbip_pad_2-PadAD2)") (class "Default")
      (node (ref "IC1") (pin "AD2") (pinfunction "rbbip_pad_2_AD2") (pintype "passive+no_connect"))
    )
    (net (code "79") (name "unconnected-(IC1B-rbbqn_pad_1-PadAA5)") (class "Default")
      (node (ref "IC1") (pin "AA5") (pinfunction "rbbqn_pad_1_AA5") (pintype "passive+no_connect"))
    )
    (net (code "80") (name "unconnected-(IC1B-rbbqn_pad_2-PadAB6)") (class "Default")
      (node (ref "IC1") (pin "AB6") (pinfunction "rbbqn_pad_2_AB6") (pintype "passive+no_connect"))
    )
    (net (code "81") (name "unconnected-(IC1B-rbbqp_pad_1-PadAB4)") (class "Default")
      (node (ref "IC1") (pin "AB4") (pinfunction "rbbqp_pad_1_AB4") (pintype "passive+no_connect"))
    )
    (net (code "82") (name "unconnected-(IC1B-rbbqp_pad_2-PadAC5)") (class "Default")
      (node (ref "IC1") (pin "AC5") (pinfunction "rbbqp_pad_2_AC5") (pintype "passive+no_connect"))
    )
    (net (code "83") (name "unconnected-(IC1B-tbbin_pad_1-PadR5)") (class "Default")
      (node (ref "IC1") (pin "R5") (pinfunction "tbbin_pad_1_R5") (pintype "passive+no_connect"))
    )
    (net (code "84") (name "unconnected-(IC1B-tbbin_pad_2-PadT6)") (class "Default")
      (node (ref "IC1") (pin "T6") (pinfunction "tbbin_pad_2_T6") (pintype "passive+no_connect"))
    )
    (net (code "85") (name "unconnected-(IC1B-tbbip_pad_1-PadT4)") (class "Default")
      (node (ref "IC1") (pin "T4") (pinfunction "tbbip_pad_1_T4") (pintype "passive+no_connect"))
    )
    (net (code "86") (name "unconnected-(IC1B-tbbip_pad_2-PadV2)") (class "Default")
      (node (ref "IC1") (pin "V2") (pinfunction "tbbip_pad_2_V2") (pintype "passive+no_connect"))
    )
    (net (code "87") (name "unconnected-(IC1B-tbbqn_pad_1-PadP2)") (class "Default")
      (node (ref "IC1") (pin "P2") (pinfunction "tbbqn_pad_1_P2") (pintype "passive+no_connect"))
    )
    (net (code "88") (name "unconnected-(IC1B-tbbqn_pad_2-PadU1)") (class "Default")
      (node (ref "IC1") (pin "U1") (pinfunction "tbbqn_pad_2_U1") (pintype "passive+no_connect"))
    )
    (net (code "89") (name "unconnected-(IC1B-tbbqp_pad_1-PadR3)") (class "Default")
      (node (ref "IC1") (pin "R3") (pinfunction "tbbqp_pad_1_R3") (pintype "passive+no_connect"))
    )
    (net (code "90") (name "unconnected-(IC1B-tbbqp_pad_2-PadU3)") (class "Default")
      (node (ref "IC1") (pin "U3") (pinfunction "tbbqp_pad_2_U3") (pintype "passive+no_connect"))
    )
    (net (code "91") (name "unconnected-(MECH2-PadMH1)") (class "Default")
      (node (ref "MECH2") (pin "MH1") (pinfunction "MH1_MH1") (pintype "passive+no_connect"))
    )
    (net (code "92") (name "unconnected-(MECH3-PadMH1)") (class "Default")
      (node (ref "MECH3") (pin "MH1") (pinfunction "MH1_MH1") (pintype "passive+no_connect"))
    )
    (net (code "93") (name "unconnected-(MECH4-PadMH1)") (class "Default")
      (node (ref "MECH4") (pin "MH1") (pinfunction "MH1_MH1") (pintype "passive+no_connect"))
    )
    (net (code "94") (name "unconnected-(MECH5-PadMH1)") (class "Default")
      (node (ref "MECH5") (pin "MH1") (pinfunction "MH1_MH1") (pintype "passive+no_connect"))
    )
    (net (code "95") (name "unconnected-(MECH6-PadMH1)") (class "Default")
      (node (ref "MECH6") (pin "MH1") (pinfunction "MH1_MH1") (pintype "passive+no_connect"))
    )
    (net (code "96") (name "unconnected-(MECH7-PadMH1)") (class "Default")
      (node (ref "MECH7") (pin "MH1") (pinfunction "MH1_MH1") (pintype "passive+no_connect"))
    )
    (net (code "97") (name "unconnected-(MECH8-PadMH1)") (class "Default")
      (node (ref "MECH8") (pin "MH1") (pinfunction "MH1_MH1") (pintype "passive+no_connect"))
    )
    (net (code "98") (name "unconnected-(MECH9-PadMH1)") (class "Default")
      (node (ref "MECH9") (pin "MH1") (pinfunction "MH1_MH1") (pintype "passive+no_connect"))
    )
    (net (code "99") (name "unconnected-(MECH10-PadMH1)") (class "Default")
      (node (ref "MECH10") (pin "MH1") (pinfunction "MH1_MH1") (pintype "passive+no_connect"))
    )
    (net (code "100") (name "unconnected-(MECH11-PadMH1)") (class "Default")
      (node (ref "MECH11") (pin "MH1") (pinfunction "MH1_MH1") (pintype "passive+no_connect"))
    )
    (net (code "101") (name "unconnected-(MECH12-PadMH1)") (class "Default")
      (node (ref "MECH12") (pin "MH1") (pinfunction "MH1_MH1") (pintype "passive+no_connect"))
    )
    (net (code "102") (name "unconnected-(MECH13-PadMH1)") (class "Default")
      (node (ref "MECH13") (pin "MH1") (pinfunction "MH1_MH1") (pintype "passive+no_connect"))
    )
    (net (code "103") (name "unconnected-(MECH20-PadMH1)") (class "Default")
      (node (ref "MECH20") (pin "MH1") (pinfunction "MH1_MH1") (pintype "passive+no_connect"))
    )
    (net (code "104") (name "unconnected-(MECH21-PadMH1)") (class "Default")
      (node (ref "MECH21") (pin "MH1") (pinfunction "MH1_MH1") (pintype "passive+no_connect"))
    )
    (net (code "105") (name "unconnected-(MECH22-PadMH1)") (class "Default")
      (node (ref "MECH22") (pin "MH1") (pinfunction "MH1_MH1") (pintype "passive+no_connect"))
    )
    (net (code "106") (name "unconnected-(MECH23-PadMH1)") (class "Default")
      (node (ref "MECH23") (pin "MH1") (pinfunction "MH1_MH1") (pintype "passive+no_connect"))
    )
    (net (code "107") (name "unconnected-(MECH24-PadMH1)") (class "Default")
      (node (ref "MECH24") (pin "MH1") (pinfunction "MH1_MH1") (pintype "passive+no_connect"))
    )
    (net (code "108") (name "unconnected-(MECH25-PadMH1)") (class "Default")
      (node (ref "MECH25") (pin "MH1") (pinfunction "MH1_MH1") (pintype "passive+no_connect"))
    )
    (net (code "109") (name "unconnected-(MECH26-PadMH1)") (class "Default")
      (node (ref "MECH26") (pin "MH1") (pinfunction "MH1_MH1") (pintype "passive+no_connect"))
    )
    (net (code "110") (name "unconnected-(MECH27-PadMH1)") (class "Default")
      (node (ref "MECH27") (pin "MH1") (pinfunction "MH1_MH1") (pintype "passive+no_connect"))
    )
    (net (code "111") (name "unconnected-(MECH28-PadMH1)") (class "Default")
      (node (ref "MECH28") (pin "MH1") (pinfunction "MH1_MH1") (pintype "passive+no_connect"))
    )
  )
)
